# Sheet1.net
KiCad netlist of a schematic drawn in Altium Designer
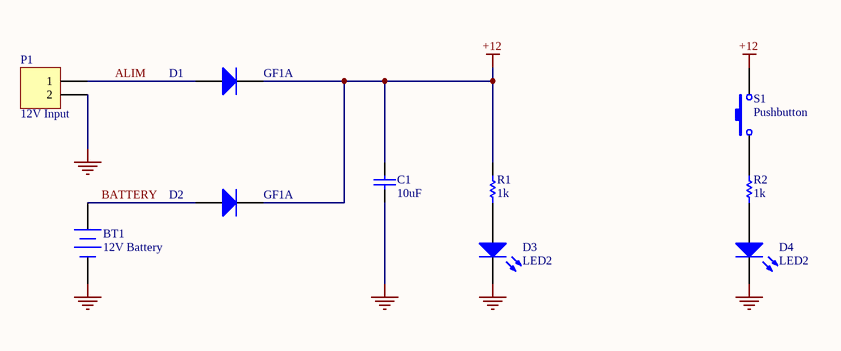
[diagram p0: Sheet1.SchDoc]

(export (version "E")
  (design (tool "Eeschema 10.0.6"))
  (components
    (comp (ref "BT1")
      (value "12V Battery")
      (footprint "BAT-2")
      (description "Multicell Battery")
      (fields (field (name "PUBLISHER") "Altium Limited"))
      (libsource (lib "Miscellaneous Devices") (part "Battery"))
    )
    (comp (ref "C1")
      (value "10uF")
      (footprint "RAD-0.3")
      (description "Capacitor")
      (fields (field (name "PUBLISHER") "Altium Limited"))
      (libsource (lib "Miscellaneous Devices") (part "Cap"))
    )
    (comp (ref "D1")
      (value "GF1A")
      (footprint "SMC")
      (description "Default Diode")
      (fields (field (name "PUBLISHER") "Altium Limited"))
      (libsource (lib "Miscellaneous Devices") (part "Diode"))
    )
    (comp (ref "D2")
      (value "GF1A")
      (footprint "SMC")
      (description "Default Diode")
      (fields (field (name "PUBLISHER") "Altium Limited"))
      (libsource (lib "Miscellaneous Devices") (part "Diode"))
    )
    (comp (ref "D3")
      (value "LED2")
      (footprint "3.2X1.6X1.1")
      (description "Typical RED, GREEN, YELLOW, AMBER GaAs LED")
      (fields (field (name "PUBLISHER") "Altium Limited"))
      (libsource (lib "Miscellaneous Devices") (part "LED2"))
    )
    (comp (ref "D4")
      (value "LED2")
      (footprint "3.2X1.6X1.1")
      (description "Typical RED, GREEN, YELLOW, AMBER GaAs LED")
      (fields (field (name "PUBLISHER") "Altium Limited"))
      (libsource (lib "Miscellaneous Devices") (part "LED2"))
    )
    (comp (ref "P1")
      (value "12V Input")
      (footprint "HDR1X2")
      (description "Header, 2-Pin")
      (fields (field (name "PUBLISHER") "Altium Limited"))
      (libsource (lib "Miscellaneous Connectors") (part "Header 2"))
    )
    (comp (ref "R1")
      (value "1k")
      (footprint "AXIAL-0.3")
      (description "Resistor")
      (fields (field (name "PUBLISHER") "Altium Limited"))
      (libsource (lib "Miscellaneous Devices") (part "Res1"))
    )
    (comp (ref "R2")
      (value "1k")
      (footprint "AXIAL-0.3")
      (description "Resistor")
      (fields (field (name "PUBLISHER") "Altium Limited"))
      (libsource (lib "Miscellaneous Devices") (part "Res1"))
    )
    (comp (ref "S1")
      (value "Pushbutton")
      (footprint "SPST-2")
      (description "Switch")
      (fields (field (name "PUBLISHER") "Altium Limited"))
      (libsource (lib "Miscellaneous Devices") (part "SW-PB"))
    )
  )
  (nets
    (net (code "1") (name "+12") (class "Default")
      (node (ref "C1") (pin "2") (pinfunction "2_2") (pintype "passive"))
      (node (ref "D1") (pin "2") (pinfunction "K_2") (pintype "passive"))
      (node (ref "D2") (pin "2") (pinfunction "K_2") (pintype "passive"))
      (node (ref "R1") (pin "2") (pinfunction "2_2") (pintype "passive"))
      (node (ref "S1") (pin "2") (pinfunction "2_2") (pintype "passive"))
    )
    (net (code "2") (name "/ALIM") (class "Default")
      (node (ref "D1") (pin "1") (pinfunction "A_1") (pintype "passive"))
      (node (ref "P1") (pin "1") (pinfunction "1_1") (pintype "passive"))
    )
    (net (code "3") (name "/BATTERY") (class "Default")
      (node (ref "BT1") (pin "1") (pinfunction "+_1") (pintype "passive"))
      (node (ref "D2") (pin "1") (pinfunction "A_1") (pintype "passive"))
    )
    (net (code "4") (name "GND") (class "Default")
      (node (ref "BT1") (pin "2") (pinfunction "-_2") (pintype "passive"))
      (node (ref "C1") (pin "1") (pinfunction "1_1") (pintype "passive"))
      (node (ref "D3") (pin "2") (pinfunction "K_2") (pintype "passive"))
      (node (ref "D4") (pin "2") (pinfunction "K_2") (pintype "passive"))
      (node (ref "P1") (pin "2") (pinfunction "2_2") (pintype "passive"))
    )
    (net (code "5") (name "Net-(D3-A)") (class "Default")
      (node (ref "D3") (pin "1") (pinfunction "A_1") (pintype "passive"))
      (node (ref "R1") (pin "1") (pinfunction "1_1") (pintype "passive"))
    )
    (net (code "6") (name "Net-(D4-A)") (class "Default")
      (node (ref "D4") (pin "1") (pinfunction "A_1") (pintype "passive"))
      (node (ref "R2") (pin "1") (pinfunction "1_1") (pintype "passive"))
    )
    (net (code "7") (name "Net-(R2-Pad2)") (class "Default")
      (node (ref "R2") (pin "2") (pinfunction "2_2") (pintype "passive"))
      (node (ref "S1") (pin "1") (pinfunction "1_1") (pintype "passive"))
    )
  )
)
